# EAGLE_PCB_Design_Project1_3_DavidSalzman.net
KiCad netlist of a schematic drawn in EAGLE
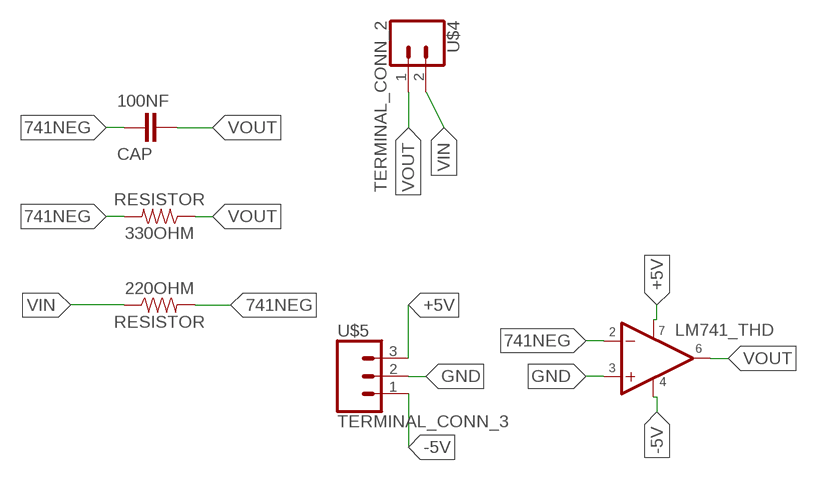
[diagram p0: schematic, sheet 1]

(export (version "E")
  (design (tool "Eeschema 10.0.6"))
  (components
    (comp (ref "100NF")
      (value "CAP")
      (footprint "eagle-import:CAP-TH")
      (libsource (lib "eagle-import") (part "CAP"))
    )
    (comp (ref "220OHM")
      (value "RESISTOR")
      (footprint "eagle-import:RESISTOR")
      (libsource (lib "eagle-import") (part "RESISTOR"))
    )
    (comp (ref "330OHM")
      (value "RESISTOR")
      (footprint "eagle-import:RESISTOR")
      (libsource (lib "eagle-import") (part "RESISTOR"))
    )
    (comp (ref "U$1")
      (value "IC-LM741")
      (footprint "eagle-import:IC-LM741")
      (libsource (lib "eagle-import") (part "IC-LM741"))
    )
    (comp (ref "U$4")
      (value "TERMINAL_CONN_2")
      (footprint "eagle-import:TERMINAL_CONN_2")
      (libsource (lib "eagle-import") (part "TERMINAL_CONN_2"))
    )
    (comp (ref "U$5")
      (value "TERMINAL_CONN_3")
      (footprint "eagle-import:TERMINAL-CONN_3")
      (libsource (lib "eagle-import") (part "TERMINAL_CONN_3"))
    )
  )
  (nets
    (net (code "1") (name "+5V") (class "Default")
      (node (ref "U$1") (pin "7") (pinfunction "7_7") (pintype "bidirectional"))
      (node (ref "U$5") (pin "3") (pinfunction "3_3") (pintype "passive"))
    )
    (net (code "2") (name "-5V") (class "Default")
      (node (ref "U$1") (pin "4") (pinfunction "4_4") (pintype "bidirectional"))
      (node (ref "U$5") (pin "1") (pinfunction "1_1") (pintype "passive"))
    )
    (net (code "3") (name "741NEG") (class "Default")
      (node (ref "100NF") (pin "1") (pinfunction "1_1") (pintype "passive"))
      (node (ref "220OHM") (pin "2") (pinfunction "2_2") (pintype "passive"))
      (node (ref "330OHM") (pin "2") (pinfunction "2_2") (pintype "passive"))
      (node (ref "U$1") (pin "2") (pinfunction "-IN_2") (pintype "input"))
    )
    (net (code "4") (name "GND") (class "Default")
      (node (ref "U$1") (pin "3") (pinfunction "+IN_3") (pintype "input"))
      (node (ref "U$5") (pin "2") (pinfunction "2_2") (pintype "passive"))
    )
    (net (code "5") (name "VIN") (class "Default")
      (node (ref "220OHM") (pin "1") (pinfunction "1_1") (pintype "passive"))
      (node (ref "U$4") (pin "2") (pinfunction "2_2") (pintype "passive"))
    )
    (net (code "6") (name "VOUT") (class "Default")
      (node (ref "100NF") (pin "2") (pinfunction "2_2") (pintype "passive"))
      (node (ref "330OHM") (pin "1") (pinfunction "1_1") (pintype "passive"))
      (node (ref "U$1") (pin "6") (pinfunction "OUT_6") (pintype "output"))
      (node (ref "U$4") (pin "1") (pinfunction "1_1") (pintype "passive"))
    )
  )
)
